# meter_hook.net
KiCad netlist of a schematic drawn in EAGLE
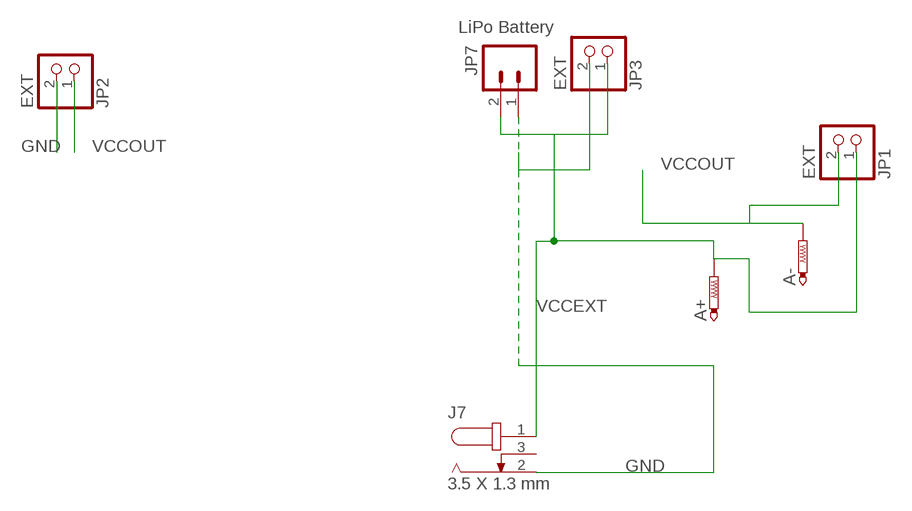
[diagram p0: schematic, sheet 1]

(export (version "E")
  (design (tool "Eeschema 10.0.6"))
  (components
    (comp (ref "A+")
      (value "PTR1PAD1-13Y")
      (footprint "eagle-import:P1-13Y")
      (libsource (lib "eagle-import") (part "PTR1PAD1-13Y"))
    )
    (comp (ref "A-")
      (value "PTR1PAD1-13Y")
      (footprint "eagle-import:P1-13Y")
      (libsource (lib "eagle-import") (part "PTR1PAD1-13Y"))
    )
    (comp (ref "J7")
      (value "3.5 X 1.3 mm")
      (footprint "eagle-import:3.5X1.3MM_DC_JACK")
      (libsource (lib "eagle-import") (part "DC_JACK_3.5X1.3MM"))
    )
    (comp (ref "JP1")
      (value "EXT")
      (footprint "eagle-import:1X02")
      (libsource (lib "eagle-import") (part "PINHD-1X2"))
    )
    (comp (ref "JP2")
      (value "EXT")
      (footprint "eagle-import:1X02")
      (libsource (lib "eagle-import") (part "PINHD-1X2"))
    )
    (comp (ref "JP3")
      (value "EXT")
      (footprint "eagle-import:1X02")
      (libsource (lib "eagle-import") (part "PINHD-1X2"))
    )
    (comp (ref "JP7")
      (value "LiPo Battery")
      (footprint "eagle-import:JST-2-PTH")
      (libsource (lib "eagle-import") (part "M02JST-PTH-2"))
    )
  )
  (nets
    (net (code "1") (name "GND") (class "Default")
      (node (ref "J7") (pin "2") (pinfunction "2_2") (pintype "passive"))
      (node (ref "JP2") (pin "2") (pinfunction "2_2") (pintype "passive"))
      (node (ref "JP3") (pin "2") (pinfunction "2_2") (pintype "passive"))
      (node (ref "JP7") (pin "1") (pinfunction "1_1") (pintype "passive"))
    )
    (net (code "2") (name "VCCEXT") (class "Default")
      (node (ref "A+") (pin "TP") (pinfunction "TP_TP") (pintype "input"))
      (node (ref "J7") (pin "1") (pinfunction "1_1") (pintype "passive"))
      (node (ref "JP1") (pin "1") (pinfunction "1_1") (pintype "passive"))
      (node (ref "JP3") (pin "1") (pinfunction "1_1") (pintype "passive"))
      (node (ref "JP7") (pin "2") (pinfunction "2_2") (pintype "passive"))
    )
    (net (code "3") (name "VCCOUT") (class "Default")
      (node (ref "A-") (pin "TP") (pinfunction "TP_TP") (pintype "input"))
      (node (ref "JP1") (pin "2") (pinfunction "2_2") (pintype "passive"))
      (node (ref "JP2") (pin "1") (pinfunction "1_1") (pintype "passive"))
    )
    (net (code "4") (name "unconnected-(J7-Pad3)") (class "Default")
      (node (ref "J7") (pin "3") (pinfunction "3_3") (pintype "passive"))
    )
  )
)
